# led_matrix_4X4.net
KiCad netlist of a schematic drawn in EAGLE
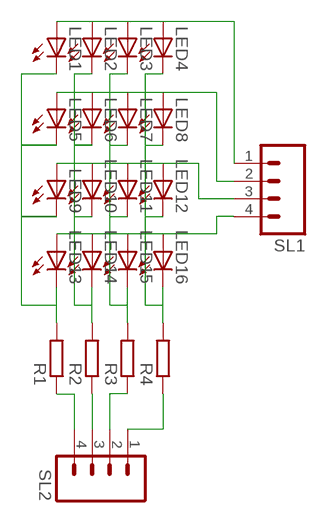
[diagram p0: schematic, sheet 1]

(export (version "E")
  (design (tool "Eeschema 10.0.6"))
  (components
    (comp (ref "LED1")
      (value "LED5MM")
      (footprint "eagle-import:LED5MM")
      (libsource (lib "eagle-import") (part "LED5MM"))
    )
    (comp (ref "LED2")
      (value "LED5MM")
      (footprint "eagle-import:LED5MM")
      (libsource (lib "eagle-import") (part "LED5MM"))
    )
    (comp (ref "LED3")
      (value "LED5MM")
      (footprint "eagle-import:LED5MM")
      (libsource (lib "eagle-import") (part "LED5MM"))
    )
    (comp (ref "LED4")
      (value "LED5MM")
      (footprint "eagle-import:LED5MM")
      (libsource (lib "eagle-import") (part "LED5MM"))
    )
    (comp (ref "LED5")
      (value "LED5MM")
      (footprint "eagle-import:LED5MM")
      (libsource (lib "eagle-import") (part "LED5MM"))
    )
    (comp (ref "LED6")
      (value "LED5MM")
      (footprint "eagle-import:LED5MM")
      (libsource (lib "eagle-import") (part "LED5MM"))
    )
    (comp (ref "LED7")
      (value "LED5MM")
      (footprint "eagle-import:LED5MM")
      (libsource (lib "eagle-import") (part "LED5MM"))
    )
    (comp (ref "LED8")
      (value "LED5MM")
      (footprint "eagle-import:LED5MM")
      (libsource (lib "eagle-import") (part "LED5MM"))
    )
    (comp (ref "LED9")
      (value "LED5MM")
      (footprint "eagle-import:LED5MM")
      (libsource (lib "eagle-import") (part "LED5MM"))
    )
    (comp (ref "LED10")
      (value "LED5MM")
      (footprint "eagle-import:LED5MM")
      (libsource (lib "eagle-import") (part "LED5MM"))
    )
    (comp (ref "LED11")
      (value "LED5MM")
      (footprint "eagle-import:LED5MM")
      (libsource (lib "eagle-import") (part "LED5MM"))
    )
    (comp (ref "LED12")
      (value "LED5MM")
      (footprint "eagle-import:LED5MM")
      (libsource (lib "eagle-import") (part "LED5MM"))
    )
    (comp (ref "LED13")
      (value "LED5MM")
      (footprint "eagle-import:LED5MM")
      (libsource (lib "eagle-import") (part "LED5MM"))
    )
    (comp (ref "LED14")
      (value "LED5MM")
      (footprint "eagle-import:LED5MM")
      (libsource (lib "eagle-import") (part "LED5MM"))
    )
    (comp (ref "LED15")
      (value "LED5MM")
      (footprint "eagle-import:LED5MM")
      (libsource (lib "eagle-import") (part "LED5MM"))
    )
    (comp (ref "LED16")
      (value "LED5MM")
      (footprint "eagle-import:LED5MM")
      (libsource (lib "eagle-import") (part "LED5MM"))
    )
    (comp (ref "R1")
      (value "R-EU_0204/7")
      (footprint "eagle-import:0204_7")
      (libsource (lib "eagle-import") (part "R-EU_0204/7"))
    )
    (comp (ref "R2")
      (value "R-EU_0204/7")
      (footprint "eagle-import:0204_7")
      (libsource (lib "eagle-import") (part "R-EU_0204/7"))
    )
    (comp (ref "R3")
      (value "R-EU_0204/7")
      (footprint "eagle-import:0204_7")
      (libsource (lib "eagle-import") (part "R-EU_0204/7"))
    )
    (comp (ref "R4")
      (value "R-EU_0204/7")
      (footprint "eagle-import:0204_7")
      (libsource (lib "eagle-import") (part "R-EU_0204/7"))
    )
    (comp (ref "SL1")
      (value "M04")
      (footprint "eagle-import:04P")
      (libsource (lib "eagle-import") (part "M04"))
    )
    (comp (ref "SL2")
      (value "M04")
      (footprint "eagle-import:04P")
      (libsource (lib "eagle-import") (part "M04"))
    )
  )
  (nets
    (net (code "1") (name "Net-(LED1-C)") (class "Default")
      (node (ref "LED1") (pin "K") (pinfunction "C_K") (pintype "passive"))
      (node (ref "LED13") (pin "K") (pinfunction "C_K") (pintype "passive"))
      (node (ref "LED5") (pin "K") (pinfunction "C_K") (pintype "passive"))
      (node (ref "LED9") (pin "K") (pinfunction "C_K") (pintype "passive"))
      (node (ref "R1") (pin "2") (pinfunction "2_2") (pintype "passive"))
    )
    (net (code "2") (name "Net-(LED1-PadA)") (class "Default")
      (node (ref "LED1") (pin "A") (pinfunction "A_A") (pintype "passive"))
      (node (ref "LED2") (pin "A") (pinfunction "A_A") (pintype "passive"))
      (node (ref "LED3") (pin "A") (pinfunction "A_A") (pintype "passive"))
      (node (ref "LED4") (pin "A") (pinfunction "A_A") (pintype "passive"))
      (node (ref "SL1") (pin "1") (pinfunction "1_1") (pintype "passive"))
    )
    (net (code "3") (name "Net-(LED5-PadA)") (class "Default")
      (node (ref "LED5") (pin "A") (pinfunction "A_A") (pintype "passive"))
      (node (ref "LED6") (pin "A") (pinfunction "A_A") (pintype "passive"))
      (node (ref "LED7") (pin "A") (pinfunction "A_A") (pintype "passive"))
      (node (ref "LED8") (pin "A") (pinfunction "A_A") (pintype "passive"))
      (node (ref "SL1") (pin "2") (pinfunction "2_2") (pintype "passive"))
    )
    (net (code "4") (name "Net-(LED10-C)") (class "Default")
      (node (ref "LED10") (pin "K") (pinfunction "C_K") (pintype "passive"))
      (node (ref "LED14") (pin "K") (pinfunction "C_K") (pintype "passive"))
      (node (ref "LED2") (pin "K") (pinfunction "C_K") (pintype "passive"))
      (node (ref "LED6") (pin "K") (pinfunction "C_K") (pintype "passive"))
      (node (ref "R2") (pin "2") (pinfunction "2_2") (pintype "passive"))
    )
    (net (code "5") (name "Net-(LED10-PadA)") (class "Default")
      (node (ref "LED10") (pin "A") (pinfunction "A_A") (pintype "passive"))
      (node (ref "LED11") (pin "A") (pinfunction "A_A") (pintype "passive"))
      (node (ref "LED12") (pin "A") (pinfunction "A_A") (pintype "passive"))
      (node (ref "LED9") (pin "A") (pinfunction "A_A") (pintype "passive"))
      (node (ref "SL1") (pin "3") (pinfunction "3_3") (pintype "passive"))
    )
    (net (code "6") (name "Net-(LED11-C)") (class "Default")
      (node (ref "LED11") (pin "K") (pinfunction "C_K") (pintype "passive"))
      (node (ref "LED15") (pin "K") (pinfunction "C_K") (pintype "passive"))
      (node (ref "LED3") (pin "K") (pinfunction "C_K") (pintype "passive"))
      (node (ref "LED7") (pin "K") (pinfunction "C_K") (pintype "passive"))
      (node (ref "R3") (pin "2") (pinfunction "2_2") (pintype "passive"))
    )
    (net (code "7") (name "Net-(LED12-C)") (class "Default")
      (node (ref "LED12") (pin "K") (pinfunction "C_K") (pintype "passive"))
      (node (ref "LED16") (pin "K") (pinfunction "C_K") (pintype "passive"))
      (node (ref "LED4") (pin "K") (pinfunction "C_K") (pintype "passive"))
      (node (ref "LED8") (pin "K") (pinfunction "C_K") (pintype "passive"))
      (node (ref "R4") (pin "2") (pinfunction "2_2") (pintype "passive"))
    )
    (net (code "8") (name "Net-(LED13-PadA)") (class "Default")
      (node (ref "LED13") (pin "A") (pinfunction "A_A") (pintype "passive"))
      (node (ref "LED14") (pin "A") (pinfunction "A_A") (pintype "passive"))
      (node (ref "LED15") (pin "A") (pinfunction "A_A") (pintype "passive"))
      (node (ref "LED16") (pin "A") (pinfunction "A_A") (pintype "passive"))
      (node (ref "SL1") (pin "4") (pinfunction "4_4") (pintype "passive"))
    )
    (net (code "9") (name "Net-(R1-Pad1)") (class "Default")
      (node (ref "R1") (pin "1") (pinfunction "1_1") (pintype "passive"))
      (node (ref "SL2") (pin "4") (pinfunction "4_4") (pintype "passive"))
    )
    (net (code "10") (name "Net-(R2-Pad1)") (class "Default")
      (node (ref "R2") (pin "1") (pinfunction "1_1") (pintype "passive"))
      (node (ref "SL2") (pin "3") (pinfunction "3_3") (pintype "passive"))
    )
    (net (code "11") (name "Net-(R3-Pad1)") (class "Default")
      (node (ref "R3") (pin "1") (pinfunction "1_1") (pintype "passive"))
      (node (ref "SL2") (pin "2") (pinfunction "2_2") (pintype "passive"))
    )
    (net (code "12") (name "Net-(R4-Pad1)") (class "Default")
      (node (ref "R4") (pin "1") (pinfunction "1_1") (pintype "passive"))
      (node (ref "SL2") (pin "1") (pinfunction "1_1") (pintype "passive"))
    )
  )
)
